# LED-PCB_DIG3.net
KiCad netlist of a schematic drawn in Altium Designer
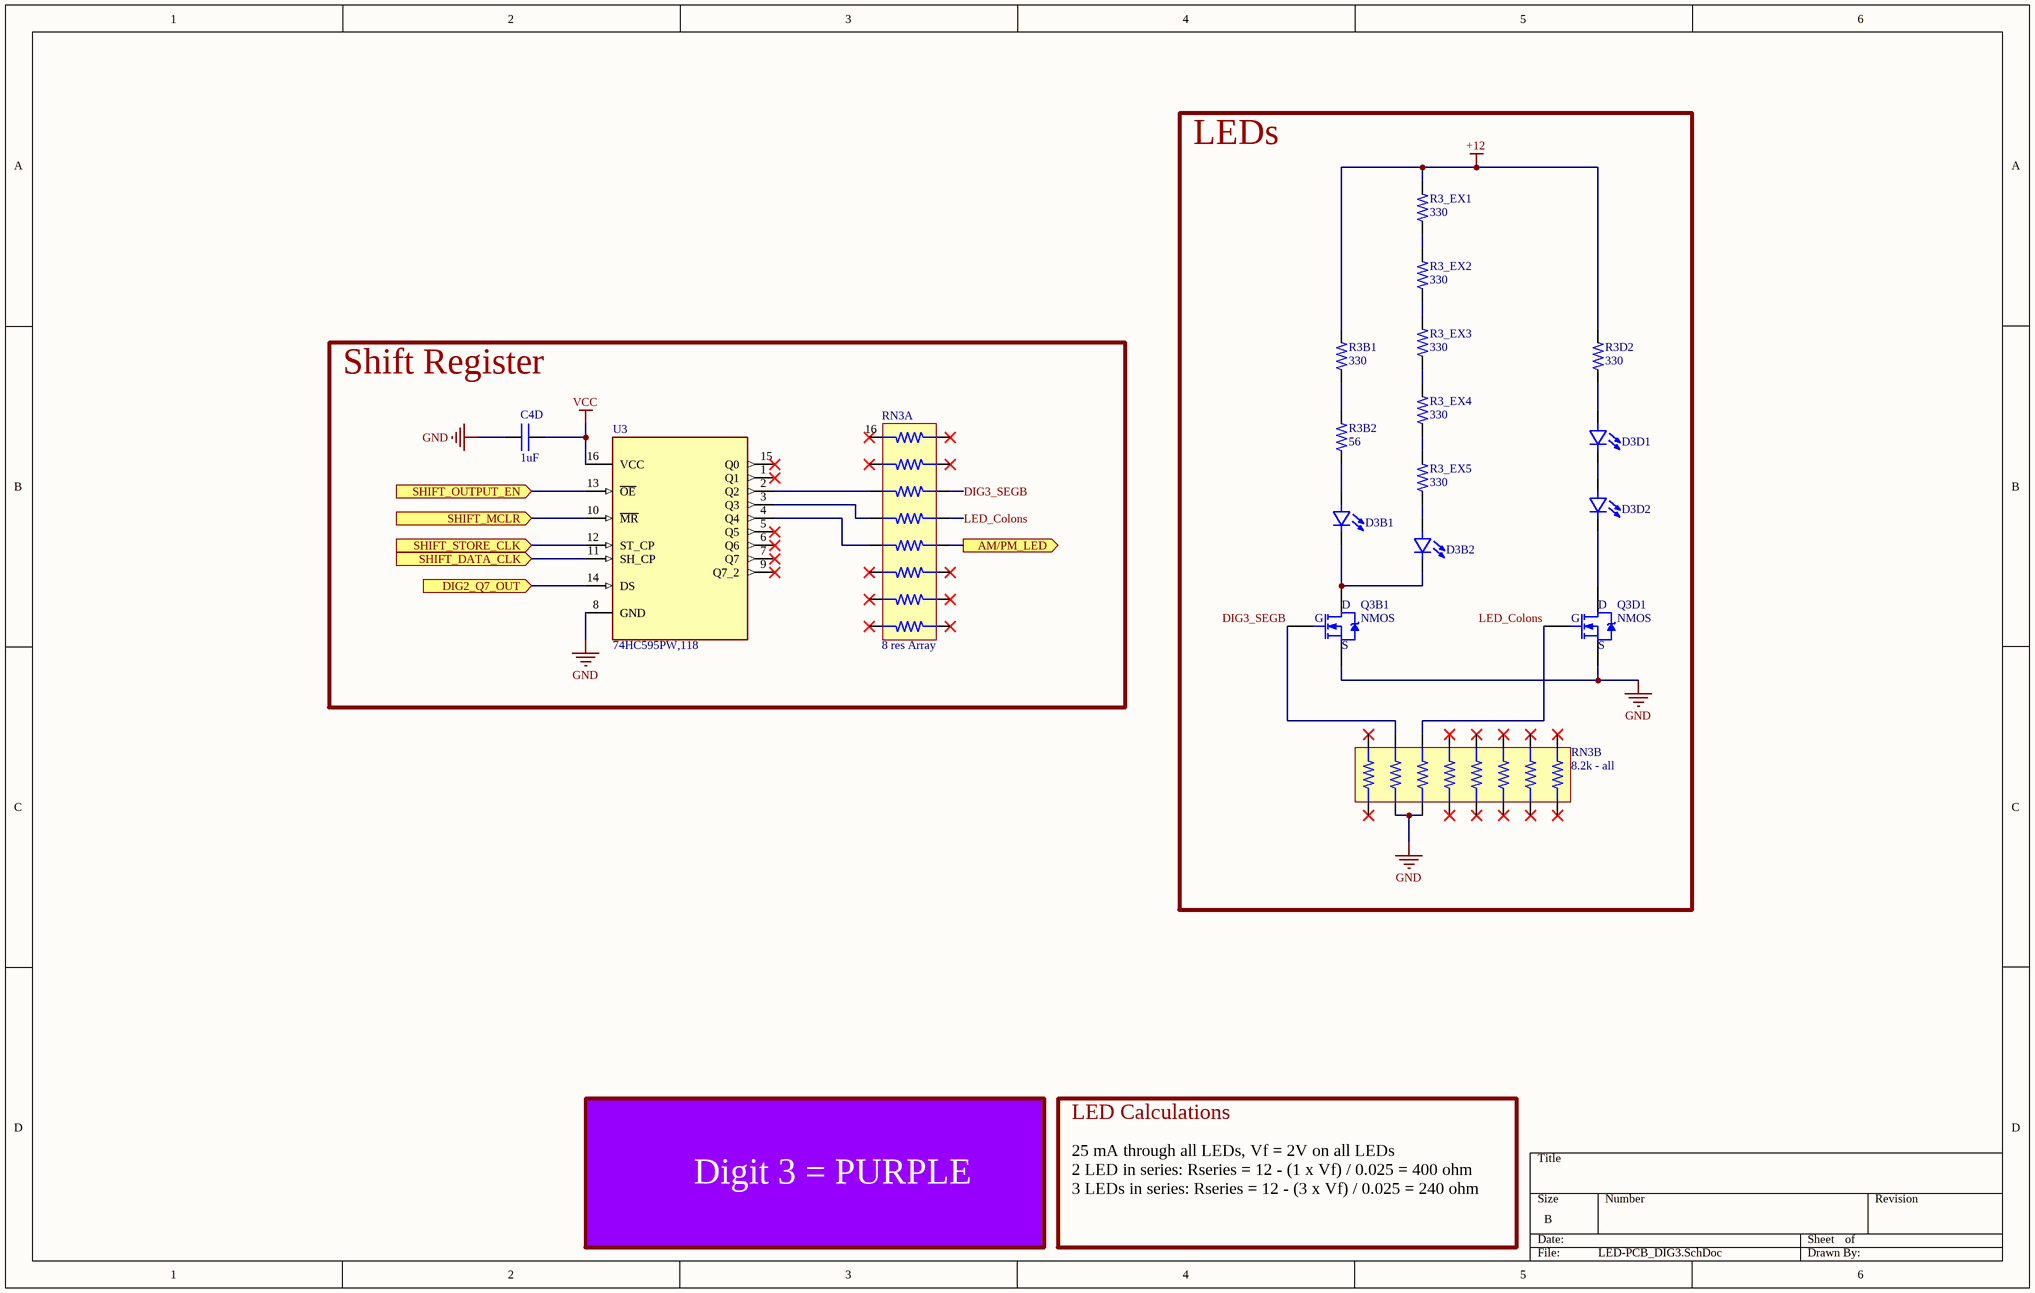
[diagram p0: LED-PCB_DIG3.SchDoc]

(export (version "E")
  (design (tool "Eeschema 10.0.6"))
  (components
    (comp (ref "C4D")
      (value "1uF")
      (footprint "sinking-clock:0402 CAP")
      (description "Capaicitor")
      (fields (field (name "MFR") "Samsung Microelectronics") (field (name "Comment") "CAP"))
      (libsource (lib "sinking-clock") (part "CAP"))
    )
    (comp (ref "D3B1")
      (value "LED - single")
      (footprint "sinking-clock:LED - 0603")
      (fields (field (name "MFR") "Wurth Elektronik"))
      (libsource (lib "sinking-clock") (part "LED - single"))
    )
    (comp (ref "D3B2")
      (value "LED - single")
      (footprint "sinking-clock:LED - 0603")
      (fields (field (name "MFR") "Wurth Elektronik"))
      (libsource (lib "sinking-clock") (part "LED - single"))
    )
    (comp (ref "D3D1")
      (value "LED - single")
      (footprint "sinking-clock:LED - 0603")
      (fields (field (name "MFR") "Wurth Elektronik"))
      (libsource (lib "sinking-clock") (part "LED - single"))
    )
    (comp (ref "D3D2")
      (value "LED - single")
      (footprint "sinking-clock:LED - 0603")
      (fields (field (name "MFR") "Wurth Elektronik"))
      (libsource (lib "sinking-clock") (part "LED - single"))
    )
    (comp (ref "Q3B1")
      (value "NMOS")
      (footprint "sinking-clock:SOT-23")
      (description "N-Channel MOSFET")
      (fields (field (name "MFR") "Diodes Incorporated"))
      (libsource (lib "sinking-clock") (part "NMOS"))
    )
    (comp (ref "Q3D1")
      (value "NMOS")
      (footprint "sinking-clock:SOT-23")
      (description "N-Channel MOSFET")
      (fields (field (name "MFR") "Diodes Incorporated"))
      (libsource (lib "sinking-clock") (part "NMOS"))
    )
    (comp (ref "R3B1")
      (value "330")
      (footprint "sinking-clock:0402 RES")
      (description "Resistor")
      (fields (field (name "MFR") "YAGEO") (field (name "Comment") "RES"))
      (libsource (lib "sinking-clock") (part "RES"))
    )
    (comp (ref "R3B2")
      (value "56")
      (footprint "sinking-clock:0402 RES")
      (description "Resistor")
      (fields (field (name "MFR") "YAGEO") (field (name "Comment") "RES"))
      (libsource (lib "sinking-clock") (part "RES"))
    )
    (comp (ref "R3D2")
      (value "330")
      (footprint "sinking-clock:0402 RES")
      (description "Resistor")
      (fields (field (name "MFR") "YAGEO") (field (name "Comment") "RES"))
      (libsource (lib "sinking-clock") (part "RES"))
    )
    (comp (ref "R3_EX1")
      (value "330")
      (footprint "sinking-clock:0402R")
      (description "Resistor")
      (fields (field (name "MFR") "YAGEO") (field (name "Comment") "RES"))
      (libsource (lib "sinking-clock") (part "RES"))
    )
    (comp (ref "R3_EX2")
      (value "330")
      (footprint "sinking-clock:0402R")
      (description "Resistor")
      (fields (field (name "MFR") "YAGEO") (field (name "Comment") "RES"))
      (libsource (lib "sinking-clock") (part "RES"))
    )
    (comp (ref "R3_EX3")
      (value "330")
      (footprint "sinking-clock:0402R")
      (description "Resistor")
      (fields (field (name "MFR") "YAGEO") (field (name "Comment") "RES"))
      (libsource (lib "sinking-clock") (part "RES"))
    )
    (comp (ref "R3_EX4")
      (value "330")
      (footprint "sinking-clock:0402R")
      (description "Resistor")
      (fields (field (name "MFR") "YAGEO") (field (name "Comment") "RES"))
      (libsource (lib "sinking-clock") (part "RES"))
    )
    (comp (ref "R3_EX5")
      (value "330")
      (footprint "sinking-clock:0402R")
      (description "Resistor")
      (fields (field (name "MFR") "YAGEO") (field (name "Comment") "RES"))
      (libsource (lib "sinking-clock") (part "RES"))
    )
    (comp (ref "RN3A")
      (value "8 res Array")
      (footprint "sinking-clock:EXB2HV331JV")
      (fields (field (name "MFR") "Panasonic Microelectronics"))
      (libsource (lib "sinking-clock") (part "8 res Array"))
    )
    (comp (ref "RN3B")
      (value "8.2k - all")
      (footprint "sinking-clock:MNR18ERAPJ822")
      (fields (field (name "MFR") "Rohm Semiconductor"))
      (libsource (lib "sinking-clock") (part "MNR18ERAPJ822"))
    )
    (comp (ref "U3")
      (value "74HC595PW,118")
      (footprint "sinking-clock:16-TSSOP")
      (description "Shift Shift Register 1 Element 8 Bit 16-TSSOP")
      (libsource (lib "sinking-clock") (part "74HC595PW,118"))
    )
  )
  (nets
    (net (code "1") (name "+12") (class "Default")
      (node (ref "R3B1") (pin "2") (pinfunction "2_2") (pintype "passive"))
      (node (ref "R3D2") (pin "2") (pinfunction "2_2") (pintype "passive"))
      (node (ref "R3_EX1") (pin "2") (pinfunction "2_2") (pintype "passive"))
    )
    (net (code "2") (name "/AM{slash}PM_LED") (class "Default")
      (node (ref "RN3A") (pin "5") (pinfunction "5_5") (pintype "passive"))
    )
    (net (code "3") (name "/DIG2_Q7_OUT") (class "Default")
      (node (ref "U3") (pin "14") (pinfunction "DS_14") (pintype "input"))
    )
    (net (code "4") (name "/DIG3_SEGB") (class "Default")
      (node (ref "Q3B1") (pin "1") (pinfunction "G_1") (pintype "passive"))
      (node (ref "RN3A") (pin "3") (pinfunction "3_3") (pintype "passive"))
      (node (ref "RN3B") (pin "15") (pinfunction "15_15") (pintype "passive"))
    )
    (net (code "5") (name "/LED_Colons") (class "Default")
      (node (ref "Q3D1") (pin "1") (pinfunction "G_1") (pintype "passive"))
      (node (ref "RN3A") (pin "4") (pinfunction "4_4") (pintype "passive"))
      (node (ref "RN3B") (pin "14") (pinfunction "14_14") (pintype "passive"))
    )
    (net (code "6") (name "/SHIFT_DATA_CLK") (class "Default")
      (node (ref "U3") (pin "11") (pinfunction "SH_CP_11") (pintype "input"))
    )
    (net (code "7") (name "/SHIFT_MCLR") (class "Default")
      (node (ref "U3") (pin "10") (pinfunction "~{MR}_10") (pintype "input"))
    )
    (net (code "8") (name "/SHIFT_OUTPUT_EN") (class "Default")
      (node (ref "U3") (pin "13") (pinfunction "~{OE}_13") (pintype "input"))
    )
    (net (code "9") (name "/SHIFT_STORE_CLK") (class "Default")
      (node (ref "U3") (pin "12") (pinfunction "ST_CP_12") (pintype "input"))
    )
    (net (code "10") (name "GND") (class "Default")
      (node (ref "C4D") (pin "2") (pinfunction "2_2") (pintype "passive"))
      (node (ref "Q3B1") (pin "2") (pinfunction "S_2") (pintype "passive"))
      (node (ref "Q3D1") (pin "2") (pinfunction "S_2") (pintype "passive"))
      (node (ref "RN3B") (pin "2") (pinfunction "2_2") (pintype "passive"))
      (node (ref "RN3B") (pin "3") (pinfunction "3_3") (pintype "passive"))
      (node (ref "U3") (pin "8") (pinfunction "GND_8") (pintype "passive"))
    )
    (net (code "11") (name "Net-(D3B1-A)") (class "Default")
      (node (ref "D3B1") (pin "1") (pinfunction "A_1") (pintype "passive"))
      (node (ref "R3B2") (pin "1") (pinfunction "1_1") (pintype "passive"))
    )
    (net (code "12") (name "Net-(D3B1-C)") (class "Default")
      (node (ref "D3B1") (pin "2") (pinfunction "C_2") (pintype "passive"))
      (node (ref "D3B2") (pin "2") (pinfunction "C_2") (pintype "passive"))
      (node (ref "Q3B1") (pin "3") (pinfunction "D_3") (pintype "passive"))
    )
    (net (code "13") (name "Net-(D3B2-A)") (class "Default")
      (node (ref "D3B2") (pin "1") (pinfunction "A_1") (pintype "passive"))
      (node (ref "R3_EX5") (pin "1") (pinfunction "1_1") (pintype "passive"))
    )
    (net (code "14") (name "Net-(D3D1-A)") (class "Default")
      (node (ref "D3D1") (pin "1") (pinfunction "A_1") (pintype "passive"))
      (node (ref "R3D2") (pin "1") (pinfunction "1_1") (pintype "passive"))
    )
    (net (code "15") (name "Net-(D3D1-C)") (class "Default")
      (node (ref "D3D1") (pin "2") (pinfunction "C_2") (pintype "passive"))
      (node (ref "D3D2") (pin "1") (pinfunction "A_1") (pintype "passive"))
    )
    (net (code "16") (name "Net-(D3D2-C)") (class "Default")
      (node (ref "D3D2") (pin "2") (pinfunction "C_2") (pintype "passive"))
      (node (ref "Q3D1") (pin "3") (pinfunction "D_3") (pintype "passive"))
    )
    (net (code "17") (name "Net-(R3B1-Pad1)") (class "Default")
      (node (ref "R3B1") (pin "1") (pinfunction "1_1") (pintype "passive"))
      (node (ref "R3B2") (pin "2") (pinfunction "2_2") (pintype "passive"))
    )
    (net (code "18") (name "Net-(R3_EX1-Pad1)") (class "Default")
      (node (ref "R3_EX1") (pin "1") (pinfunction "1_1") (pintype "passive"))
      (node (ref "R3_EX2") (pin "2") (pinfunction "2_2") (pintype "passive"))
    )
    (net (code "19") (name "Net-(R3_EX2-Pad1)") (class "Default")
      (node (ref "R3_EX2") (pin "1") (pinfunction "1_1") (pintype "passive"))
      (node (ref "R3_EX3") (pin "2") (pinfunction "2_2") (pintype "passive"))
    )
    (net (code "20") (name "Net-(R3_EX3-Pad1)") (class "Default")
      (node (ref "R3_EX3") (pin "1") (pinfunction "1_1") (pintype "passive"))
      (node (ref "R3_EX4") (pin "2") (pinfunction "2_2") (pintype "passive"))
    )
    (net (code "21") (name "Net-(R3_EX4-Pad1)") (class "Default")
      (node (ref "R3_EX4") (pin "1") (pinfunction "1_1") (pintype "passive"))
      (node (ref "R3_EX5") (pin "2") (pinfunction "2_2") (pintype "passive"))
    )
    (net (code "22") (name "Net-(U3-Q2)") (class "Default")
      (node (ref "RN3A") (pin "14") (pinfunction "14_14") (pintype "passive"))
      (node (ref "U3") (pin "2") (pinfunction "Q2_2") (pintype "output"))
    )
    (net (code "23") (name "Net-(U3-Q3)") (class "Default")
      (node (ref "RN3A") (pin "13") (pinfunction "13_13") (pintype "passive"))
      (node (ref "U3") (pin "3") (pinfunction "Q3_3") (pintype "output"))
    )
    (net (code "24") (name "Net-(U3-Q4)") (class "Default")
      (node (ref "RN3A") (pin "12") (pinfunction "12_12") (pintype "passive"))
      (node (ref "U3") (pin "4") (pinfunction "Q4_4") (pintype "output"))
    )
    (net (code "25") (name "VCC") (class "Default")
      (node (ref "C4D") (pin "1") (pinfunction "1_1") (pintype "passive"))
      (node (ref "U3") (pin "16") (pinfunction "VCC_16") (pintype "power_in"))
    )
    (net (code "26") (name "unconnected-(RN3A-Pad1)") (class "Default")
      (node (ref "RN3A") (pin "1") (pinfunction "1_1") (pintype "passive+no_connect"))
    )
    (net (code "27") (name "unconnected-(RN3A-Pad2)") (class "Default")
      (node (ref "RN3A") (pin "2") (pinfunction "2_2") (pintype "passive+no_connect"))
    )
    (net (code "28") (name "unconnected-(RN3A-Pad6)") (class "Default")
      (node (ref "RN3A") (pin "6") (pinfunction "6_6") (pintype "passive+no_connect"))
    )
    (net (code "29") (name "unconnected-(RN3A-Pad7)") (class "Default")
      (node (ref "RN3A") (pin "7") (pinfunction "7_7") (pintype "passive+no_connect"))
    )
    (net (code "30") (name "unconnected-(RN3A-Pad8)") (class "Default")
      (node (ref "RN3A") (pin "8") (pinfunction "8_8") (pintype "passive+no_connect"))
    )
    (net (code "31") (name "unconnected-(RN3A-Pad9)") (class "Default")
      (node (ref "RN3A") (pin "9") (pinfunction "9_9") (pintype "passive+no_connect"))
    )
    (net (code "32") (name "unconnected-(RN3A-Pad10)") (class "Default")
      (node (ref "RN3A") (pin "10") (pinfunction "10_10") (pintype "passive+no_connect"))
    )
    (net (code "33") (name "unconnected-(RN3A-Pad11)") (class "Default")
      (node (ref "RN3A") (pin "11") (pinfunction "11_11") (pintype "passive+no_connect"))
    )
    (net (code "34") (name "unconnected-(RN3A-Pad15)") (class "Default")
      (node (ref "RN3A") (pin "15") (pinfunction "15_15") (pintype "passive+no_connect"))
    )
    (net (code "35") (name "unconnected-(RN3A-Pad16)") (class "Default")
      (node (ref "RN3A") (pin "16") (pinfunction "16_16") (pintype "passive+no_connect"))
    )
    (net (code "36") (name "unconnected-(RN3B-Pad1)") (class "Default")
      (node (ref "RN3B") (pin "1") (pinfunction "1_1") (pintype "passive+no_connect"))
    )
    (net (code "37") (name "unconnected-(RN3B-Pad4)") (class "Default")
      (node (ref "RN3B") (pin "4") (pinfunction "4_4") (pintype "passive+no_connect"))
    )
    (net (code "38") (name "unconnected-(RN3B-Pad5)") (class "Default")
      (node (ref "RN3B") (pin "5") (pinfunction "5_5") (pintype "passive+no_connect"))
    )
    (net (code "39") (name "unconnected-(RN3B-Pad6)") (class "Default")
      (node (ref "RN3B") (pin "6") (pinfunction "6_6") (pintype "passive+no_connect"))
    )
    (net (code "40") (name "unconnected-(RN3B-Pad7)") (class "Default")
      (node (ref "RN3B") (pin "7") (pinfunction "7_7") (pintype "passive+no_connect"))
    )
    (net (code "41") (name "unconnected-(RN3B-Pad8)") (class "Default")
      (node (ref "RN3B") (pin "8") (pinfunction "8_8") (pintype "passive+no_connect"))
    )
    (net (code "42") (name "unconnected-(RN3B-Pad9)") (class "Default")
      (node (ref "RN3B") (pin "9") (pinfunction "9_9") (pintype "passive+no_connect"))
    )
    (net (code "43") (name "unconnected-(RN3B-Pad10)") (class "Default")
      (node (ref "RN3B") (pin "10") (pinfunction "10_10") (pintype "passive+no_connect"))
    )
    (net (code "44") (name "unconnected-(RN3B-Pad11)") (class "Default")
      (node (ref "RN3B") (pin "11") (pinfunction "11_11") (pintype "passive+no_connect"))
    )
    (net (code "45") (name "unconnected-(RN3B-Pad12)") (class "Default")
      (node (ref "RN3B") (pin "12") (pinfunction "12_12") (pintype "passive+no_connect"))
    )
    (net (code "46") (name "unconnected-(RN3B-Pad13)") (class "Default")
      (node (ref "RN3B") (pin "13") (pinfunction "13_13") (pintype "passive+no_connect"))
    )
    (net (code "47") (name "unconnected-(RN3B-Pad16)") (class "Default")
      (node (ref "RN3B") (pin "16") (pinfunction "16_16") (pintype "passive+no_connect"))
    )
    (net (code "48") (name "unconnected-(U3-Q0-Pad15)") (class "Default")
      (node (ref "U3") (pin "15") (pinfunction "Q0_15") (pintype "output+no_connect"))
    )
    (net (code "49") (name "unconnected-(U3-Q1-Pad1)") (class "Default")
      (node (ref "U3") (pin "1") (pinfunction "Q1_1") (pintype "output+no_connect"))
    )
    (net (code "50") (name "unconnected-(U3-Q5-Pad5)") (class "Default")
      (node (ref "U3") (pin "5") (pinfunction "Q5_5") (pintype "output+no_connect"))
    )
    (net (code "51") (name "unconnected-(U3-Q6-Pad6)") (class "Default")
      (node (ref "U3") (pin "6") (pinfunction "Q6_6") (pintype "output+no_connect"))
    )
    (net (code "52") (name "unconnected-(U3-Q7-Pad7)") (class "Default")
      (node (ref "U3") (pin "7") (pinfunction "Q7_7") (pintype "output+no_connect"))
    )
    (net (code "53") (name "unconnected-(U3-Q7_2-Pad9)") (class "Default")
      (node (ref "U3") (pin "9") (pinfunction "Q7_2_9") (pintype "output+no_connect"))
    )
  )
)
